# buckConverterRev3.net
KiCad netlist of a schematic drawn in EAGLE
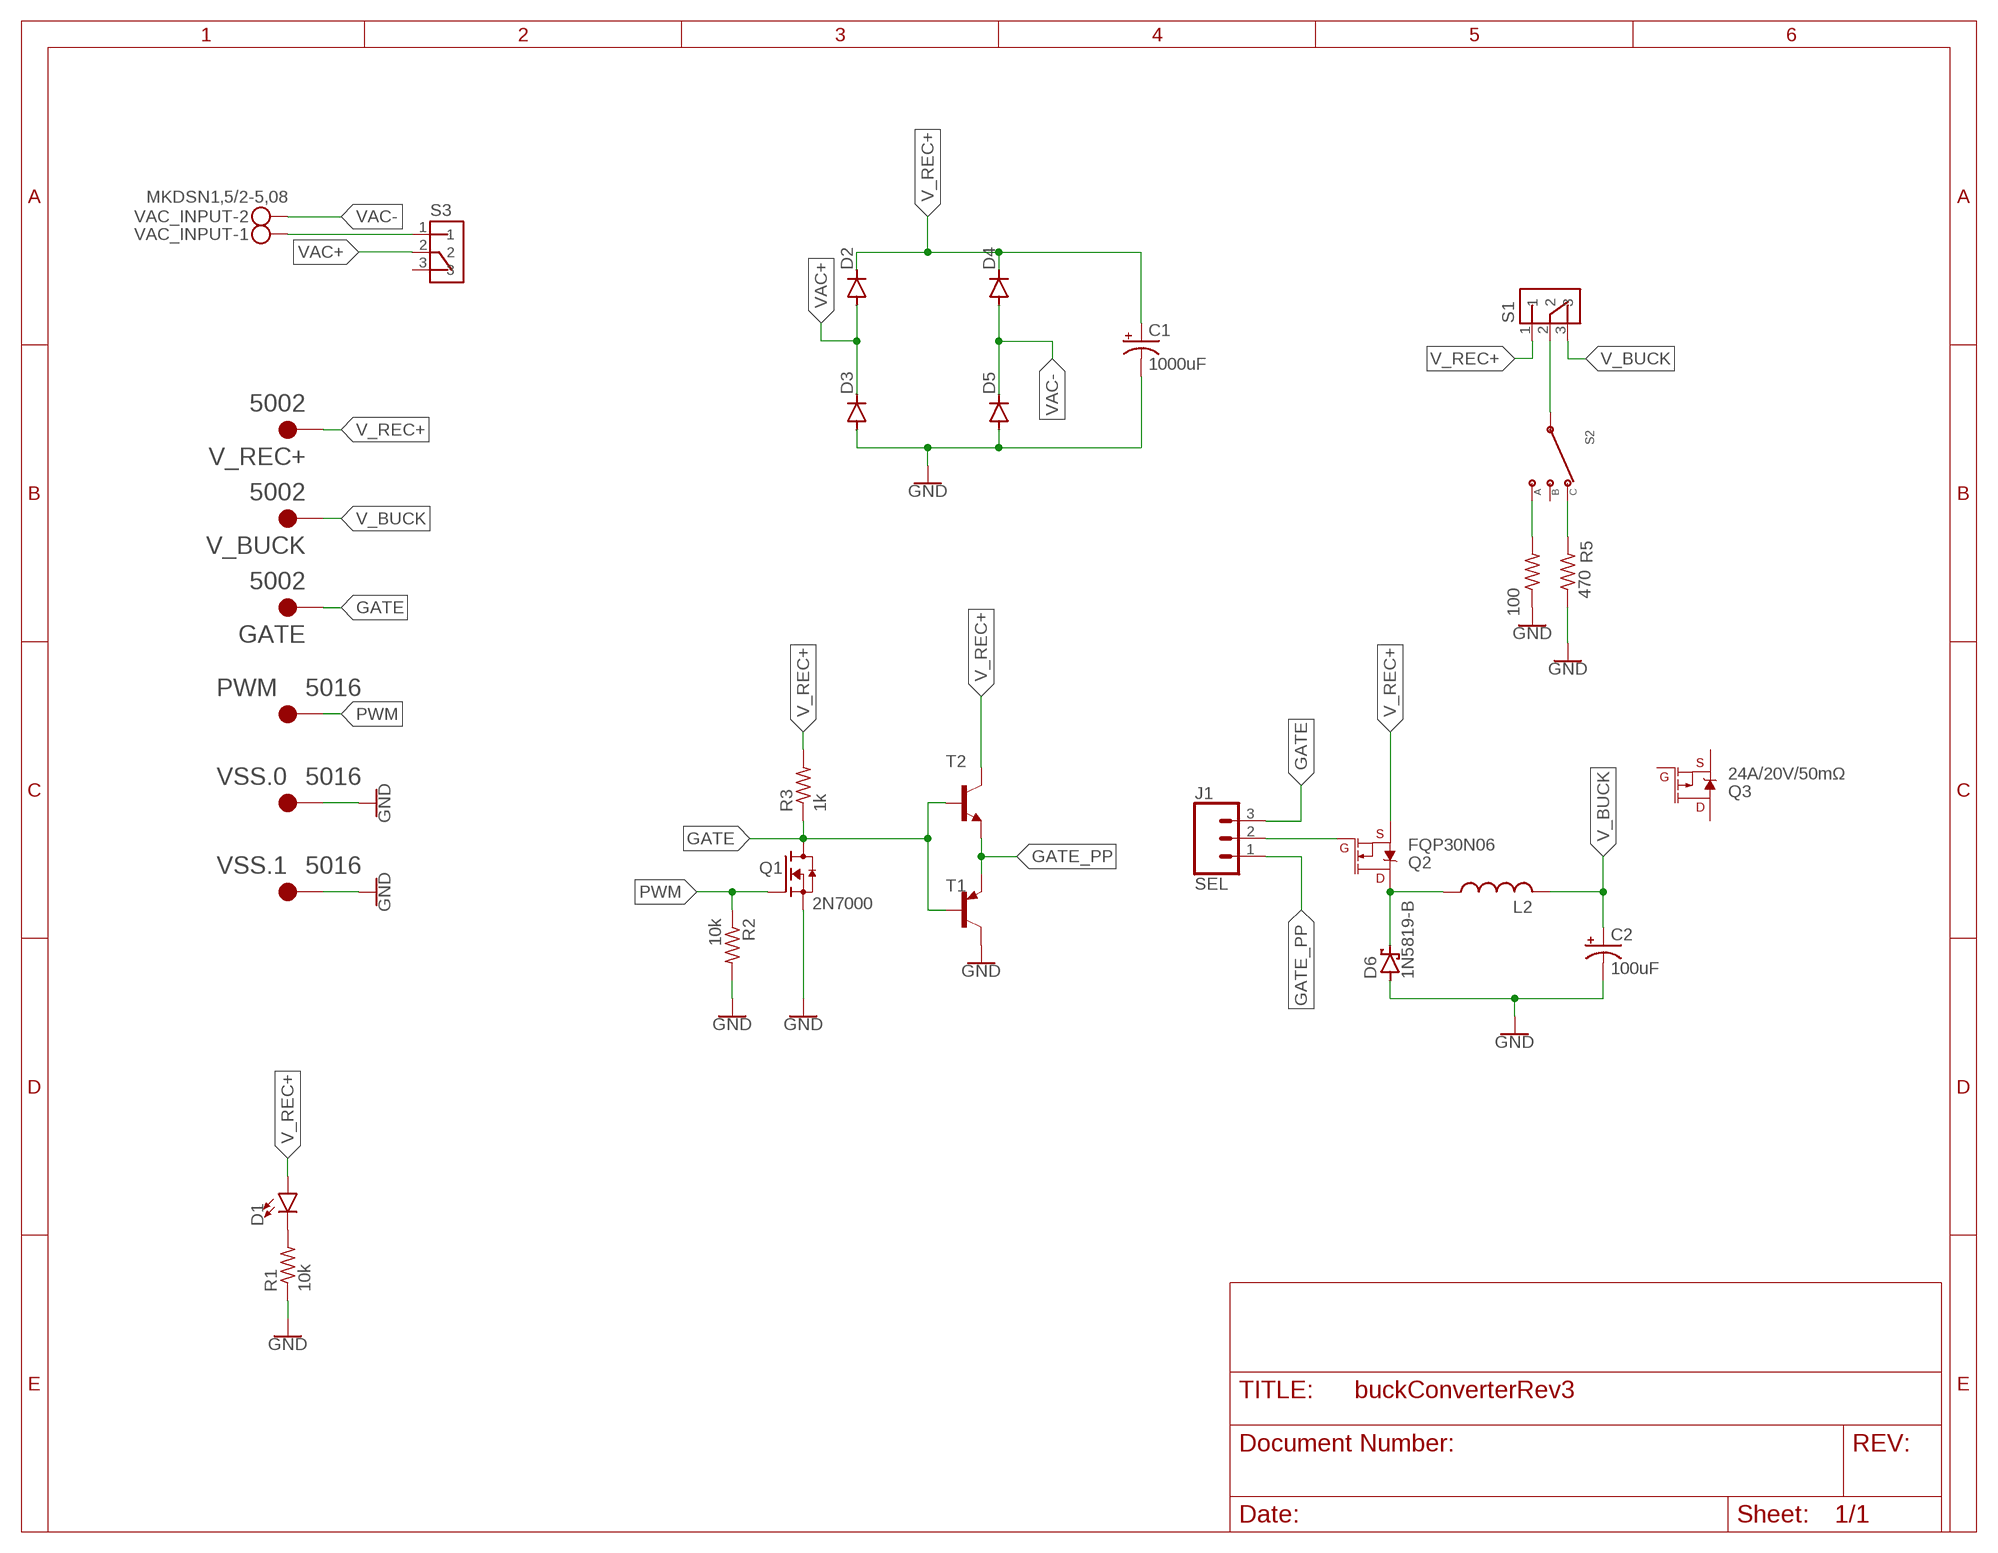
[diagram p0: schematic, sheet 1]

(export (version "E")
  (design (tool "Eeschema 10.0.6"))
  (components
    (comp (ref "C1")
      (value "1000uF")
      (footprint "eagle-import:SANYO-OSCON_F13")
      (libsource (lib "eagle-import") (part "CPOL-USSANYO_F13"))
    )
    (comp (ref "C2")
      (value "100uF")
      (footprint "eagle-import:SANYO-OSCON_C")
      (libsource (lib "eagle-import") (part "CPOL-USSANYO_C"))
    )
    (comp (ref "D1")
      (value "LED5MM")
      (footprint "eagle-import:LED_5MM")
      (libsource (lib "eagle-import") (part "LED5MM"))
    )
    (comp (ref "D2")
      (value "DIODE-DO41-7.6")
      (footprint "eagle-import:DO41-7.6")
      (libsource (lib "eagle-import") (part "DIODE-DO41-7.6"))
    )
    (comp (ref "D3")
      (value "DIODE-DO41-7.6")
      (footprint "eagle-import:DO41-7.6")
      (libsource (lib "eagle-import") (part "DIODE-DO41-7.6"))
    )
    (comp (ref "D4")
      (value "DIODE-DO41-7.6")
      (footprint "eagle-import:DO41-7.6")
      (libsource (lib "eagle-import") (part "DIODE-DO41-7.6"))
    )
    (comp (ref "D5")
      (value "DIODE-DO41-7.6")
      (footprint "eagle-import:DO41-7.6")
      (libsource (lib "eagle-import") (part "DIODE-DO41-7.6"))
    )
    (comp (ref "D6")
      (value "1N5819-B")
      (footprint "eagle-import:DO41-7.6")
      (libsource (lib "eagle-import") (part "1N5819-B"))
    )
    (comp (ref "GATE")
      (value "5002")
      (footprint "eagle-import:KEYSTONE_5002")
      (fields (field (name "MANUFACTURER") "Keystone"))
      (libsource (lib "eagle-import") (part "5002"))
    )
    (comp (ref "J1")
      (value "SEL")
      (footprint "eagle-import:1X03_LOCK_LONGPADS")
      (libsource (lib "eagle-import") (part "CONN_03LOCK_LONGPADS"))
    )
    (comp (ref "L2")
      (value "L-US6000-XXX-RC")
      (footprint "eagle-import:6000-XXXX-RC")
      (libsource (lib "eagle-import") (part "L-US6000-XXX-RC"))
    )
    (comp (ref "PWM")
      (value "5016")
      (footprint "eagle-import:KEYSTONE_5016")
      (fields (field (name "MANUFACTURER") "Keystone Electronics"))
      (libsource (lib "eagle-import") (part "5016"))
    )
    (comp (ref "Q1")
      (value "2N7000")
      (footprint "eagle-import:TO92254P458H750-3")
      (fields (field (name "MANUFACTURER") "Diotec Semiconductor"))
      (libsource (lib "eagle-import") (part "2N7000"))
    )
    (comp (ref "Q2")
      (value "FQP30N06")
      (footprint "eagle-import:TO220V")
      (libsource (lib "eagle-import") (part "MOSFET-NCH-FQP30N06L"))
    )
    (comp (ref "Q3")
      (value "24A/20V/50mΩ")
      (footprint "eagle-import:TO220V")
      (libsource (lib "eagle-import") (part "MOSFET_PCH-NDP6020P"))
    )
    (comp (ref "R1")
      (value "10k")
      (footprint "eagle-import:0207_10")
      (libsource (lib "eagle-import") (part "R-US_0207/10"))
    )
    (comp (ref "R2")
      (value "10k")
      (footprint "eagle-import:0207_10")
      (libsource (lib "eagle-import") (part "R-US_0207/10"))
    )
    (comp (ref "R3")
      (value "1k")
      (footprint "eagle-import:0207_10")
      (libsource (lib "eagle-import") (part "R-US_0207/10"))
    )
    (comp (ref "R4")
      (value "100")
      (footprint "eagle-import:0617_22")
      (libsource (lib "eagle-import") (part "R-US_0617/22"))
    )
    (comp (ref "R5")
      (value "470")
      (footprint "eagle-import:0309_12")
      (libsource (lib "eagle-import") (part "R-US_0309/12"))
    )
    (comp (ref "S1")
      (value "OS102011MS2QN1")
      (footprint "eagle-import:SW_OS102011MS2QN1")
      (fields (field (name "MF") "C&K"))
      (libsource (lib "eagle-import") (part "OS102011MS2QN1"))
    )
    (comp (ref "S2")
      (value "OS103011MS8QP1")
      (footprint "eagle-import:OS102011MS8QP1")
      (fields (field (name "MF") "C&K"))
      (libsource (lib "eagle-import") (part "OS103011MS8QP1"))
    )
    (comp (ref "S3")
      (value "ON/OFF")
      (footprint "eagle-import:SW_OS102011MS2QN1")
      (fields (field (name "MF") "C&K") (field (name "MP") "OS102011MS2QN1"))
      (libsource (lib "eagle-import") (part "OS102011MS2QN1"))
    )
    (comp (ref "T1")
      (value "2N3906-PNP-TO92-EBC")
      (footprint "eagle-import:TO92-EBC")
      (libsource (lib "eagle-import") (part "-PNP-TO92-EBC2N3906"))
    )
    (comp (ref "T2")
      (value "2N3904-NPN-TO92-EBC")
      (footprint "eagle-import:TO92-EBC")
      (libsource (lib "eagle-import") (part "-NPN-TO92-EBC2N3904"))
    )
    (comp (ref "VAC_INPUT")
      (value "MKDSN1,5/2-5,08")
      (footprint "eagle-import:MKDSN1,5_2-5,08")
      (libsource (lib "eagle-import") (part "MKDSN1,5/2-5,08"))
    )
    (comp (ref "VSS.0")
      (value "5016")
      (footprint "eagle-import:KEYSTONE_5016")
      (fields (field (name "MANUFACTURER") "Keystone Electronics"))
      (libsource (lib "eagle-import") (part "5016"))
    )
    (comp (ref "VSS.1")
      (value "5016")
      (footprint "eagle-import:KEYSTONE_5016")
      (fields (field (name "MANUFACTURER") "Keystone Electronics"))
      (libsource (lib "eagle-import") (part "5016"))
    )
    (comp (ref "V_BUCK")
      (value "5002")
      (footprint "eagle-import:KEYSTONE_5002")
      (fields (field (name "MANUFACTURER") "Keystone"))
      (libsource (lib "eagle-import") (part "5002"))
    )
    (comp (ref "V_REC+")
      (value "5002")
      (footprint "eagle-import:KEYSTONE_5002")
      (fields (field (name "MANUFACTURER") "Keystone"))
      (libsource (lib "eagle-import") (part "5002"))
    )
  )
  (nets
    (net (code "1") (name "GATE") (class "Default")
      (node (ref "GATE") (pin "TP") (pinfunction "TP_TP") (pintype "passive"))
      (node (ref "J1") (pin "3") (pinfunction "3_3") (pintype "passive"))
      (node (ref "Q1") (pin "3") (pinfunction "D_3") (pintype "passive"))
      (node (ref "R3") (pin "1") (pinfunction "1_1") (pintype "passive"))
      (node (ref "T1") (pin "B") (pinfunction "B_B") (pintype "passive"))
      (node (ref "T2") (pin "B") (pinfunction "B_B") (pintype "passive"))
    )
    (net (code "2") (name "GATE_PP") (class "Default")
      (node (ref "J1") (pin "1") (pinfunction "1_1") (pintype "passive"))
      (node (ref "T1") (pin "E") (pinfunction "E_E") (pintype "passive"))
      (node (ref "T2") (pin "E") (pinfunction "E_E") (pintype "passive"))
    )
    (net (code "3") (name "GND") (class "Default")
      (node (ref "C1") (pin "-") (pinfunction "-_-") (pintype "passive"))
      (node (ref "C2") (pin "-") (pinfunction "-_-") (pintype "passive"))
      (node (ref "D3") (pin "A") (pinfunction "A_A") (pintype "passive"))
      (node (ref "D5") (pin "A") (pinfunction "A_A") (pintype "passive"))
      (node (ref "D6") (pin "A") (pinfunction "A_A") (pintype "passive"))
      (node (ref "Q1") (pin "1") (pinfunction "S_1") (pintype "passive"))
      (node (ref "R1") (pin "1") (pinfunction "1_1") (pintype "passive"))
      (node (ref "R2") (pin "2") (pinfunction "2_2") (pintype "passive"))
      (node (ref "R4") (pin "1") (pinfunction "1_1") (pintype "passive"))
      (node (ref "R5") (pin "1") (pinfunction "1_1") (pintype "passive"))
      (node (ref "T1") (pin "C") (pinfunction "C_C") (pintype "passive"))
      (node (ref "VSS.0") (pin "TP") (pinfunction "TP_TP") (pintype "passive"))
      (node (ref "VSS.1") (pin "TP") (pinfunction "TP_TP") (pintype "passive"))
    )
    (net (code "4") (name "Net-(D1-C)") (class "Default")
      (node (ref "D1") (pin "K") (pinfunction "C_K") (pintype "passive"))
      (node (ref "R1") (pin "2") (pinfunction "2_2") (pintype "passive"))
    )
    (net (code "5") (name "Net-(Q2-D)") (class "Default")
      (node (ref "D6") (pin "C") (pinfunction "C_C") (pintype "passive"))
      (node (ref "L2") (pin "1") (pinfunction "1_1") (pintype "passive"))
      (node (ref "Q2") (pin "2") (pinfunction "D_2") (pintype "bidirectional"))
    )
    (net (code "6") (name "Net-(Q2-G)") (class "Default")
      (node (ref "J1") (pin "2") (pinfunction "2_2") (pintype "passive"))
      (node (ref "Q2") (pin "1") (pinfunction "G_1") (pintype "bidirectional"))
    )
    (net (code "7") (name "Net-(R4-Pad2)") (class "Default")
      (node (ref "R4") (pin "2") (pinfunction "2_2") (pintype "passive"))
      (node (ref "S2") (pin "1") (pinfunction "1_1") (pintype "bidirectional"))
    )
    (net (code "8") (name "Net-(S2-3)") (class "Default")
      (node (ref "R5") (pin "2") (pinfunction "2_2") (pintype "passive"))
      (node (ref "S2") (pin "4") (pinfunction "3_4") (pintype "bidirectional"))
    )
    (net (code "9") (name "Net-(S2-C)") (class "Default")
      (node (ref "S1") (pin "2") (pinfunction "2_2") (pintype "passive"))
      (node (ref "S2") (pin "2") (pinfunction "C_2") (pintype "bidirectional"))
    )
    (net (code "10") (name "Net-(VAC_INPUTA-KL)") (class "Default")
      (node (ref "S3") (pin "1") (pinfunction "1_1") (pintype "passive"))
      (node (ref "VAC_INPUT") (pin "1") (pinfunction "KL_1") (pintype "passive"))
    )
    (net (code "11") (name "PWM") (class "Default")
      (node (ref "PWM") (pin "TP") (pinfunction "TP_TP") (pintype "passive"))
      (node (ref "Q1") (pin "2") (pinfunction "G_2") (pintype "passive"))
      (node (ref "R2") (pin "1") (pinfunction "1_1") (pintype "passive"))
    )
    (net (code "12") (name "VAC+") (class "Default")
      (node (ref "D2") (pin "A") (pinfunction "A_A") (pintype "passive"))
      (node (ref "D3") (pin "C") (pinfunction "C_C") (pintype "passive"))
      (node (ref "S3") (pin "2") (pinfunction "2_2") (pintype "passive"))
    )
    (net (code "13") (name "VAC-") (class "Default")
      (node (ref "D4") (pin "A") (pinfunction "A_A") (pintype "passive"))
      (node (ref "D5") (pin "C") (pinfunction "C_C") (pintype "passive"))
      (node (ref "VAC_INPUT") (pin "2") (pinfunction "KL_2") (pintype "passive"))
    )
    (net (code "14") (name "V_BUCK") (class "Default")
      (node (ref "C2") (pin "+") (pinfunction "+_+") (pintype "passive"))
      (node (ref "L2") (pin "2") (pinfunction "2_2") (pintype "passive"))
      (node (ref "S1") (pin "3") (pinfunction "3_3") (pintype "passive"))
      (node (ref "V_BUCK") (pin "TP") (pinfunction "TP_TP") (pintype "passive"))
    )
    (net (code "15") (name "V_REC+") (class "Default")
      (node (ref "C1") (pin "+") (pinfunction "+_+") (pintype "passive"))
      (node (ref "D1") (pin "A") (pinfunction "A_A") (pintype "passive"))
      (node (ref "D2") (pin "C") (pinfunction "C_C") (pintype "passive"))
      (node (ref "D4") (pin "C") (pinfunction "C_C") (pintype "passive"))
      (node (ref "Q2") (pin "3") (pinfunction "S_3") (pintype "bidirectional"))
      (node (ref "R3") (pin "2") (pinfunction "2_2") (pintype "passive"))
      (node (ref "S1") (pin "1") (pinfunction "1_1") (pintype "passive"))
      (node (ref "T2") (pin "C") (pinfunction "C_C") (pintype "passive"))
      (node (ref "V_REC+") (pin "TP") (pinfunction "TP_TP") (pintype "passive"))
    )
    (net (code "16") (name "unconnected-(Q3-D-Pad2)") (class "Default")
      (node (ref "Q3") (pin "2") (pinfunction "D_2") (pintype "bidirectional"))
    )
    (net (code "17") (name "unconnected-(Q3-G-Pad1)") (class "Default")
      (node (ref "Q3") (pin "1") (pinfunction "G_1") (pintype "bidirectional"))
    )
    (net (code "18") (name "unconnected-(Q3-S-Pad3)") (class "Default")
      (node (ref "Q3") (pin "3") (pinfunction "S_3") (pintype "bidirectional"))
    )
    (net (code "19") (name "unconnected-(S2-2-Pad3)") (class "Default")
      (node (ref "S2") (pin "3") (pinfunction "2_3") (pintype "bidirectional"))
    )
    (net (code "20") (name "unconnected-(S3-Pad3)") (class "Default")
      (node (ref "S3") (pin "3") (pinfunction "3_3") (pintype "passive"))
    )
  )
)
